# FiberLEDDouble.net
KiCad netlist of a schematic drawn in EAGLE
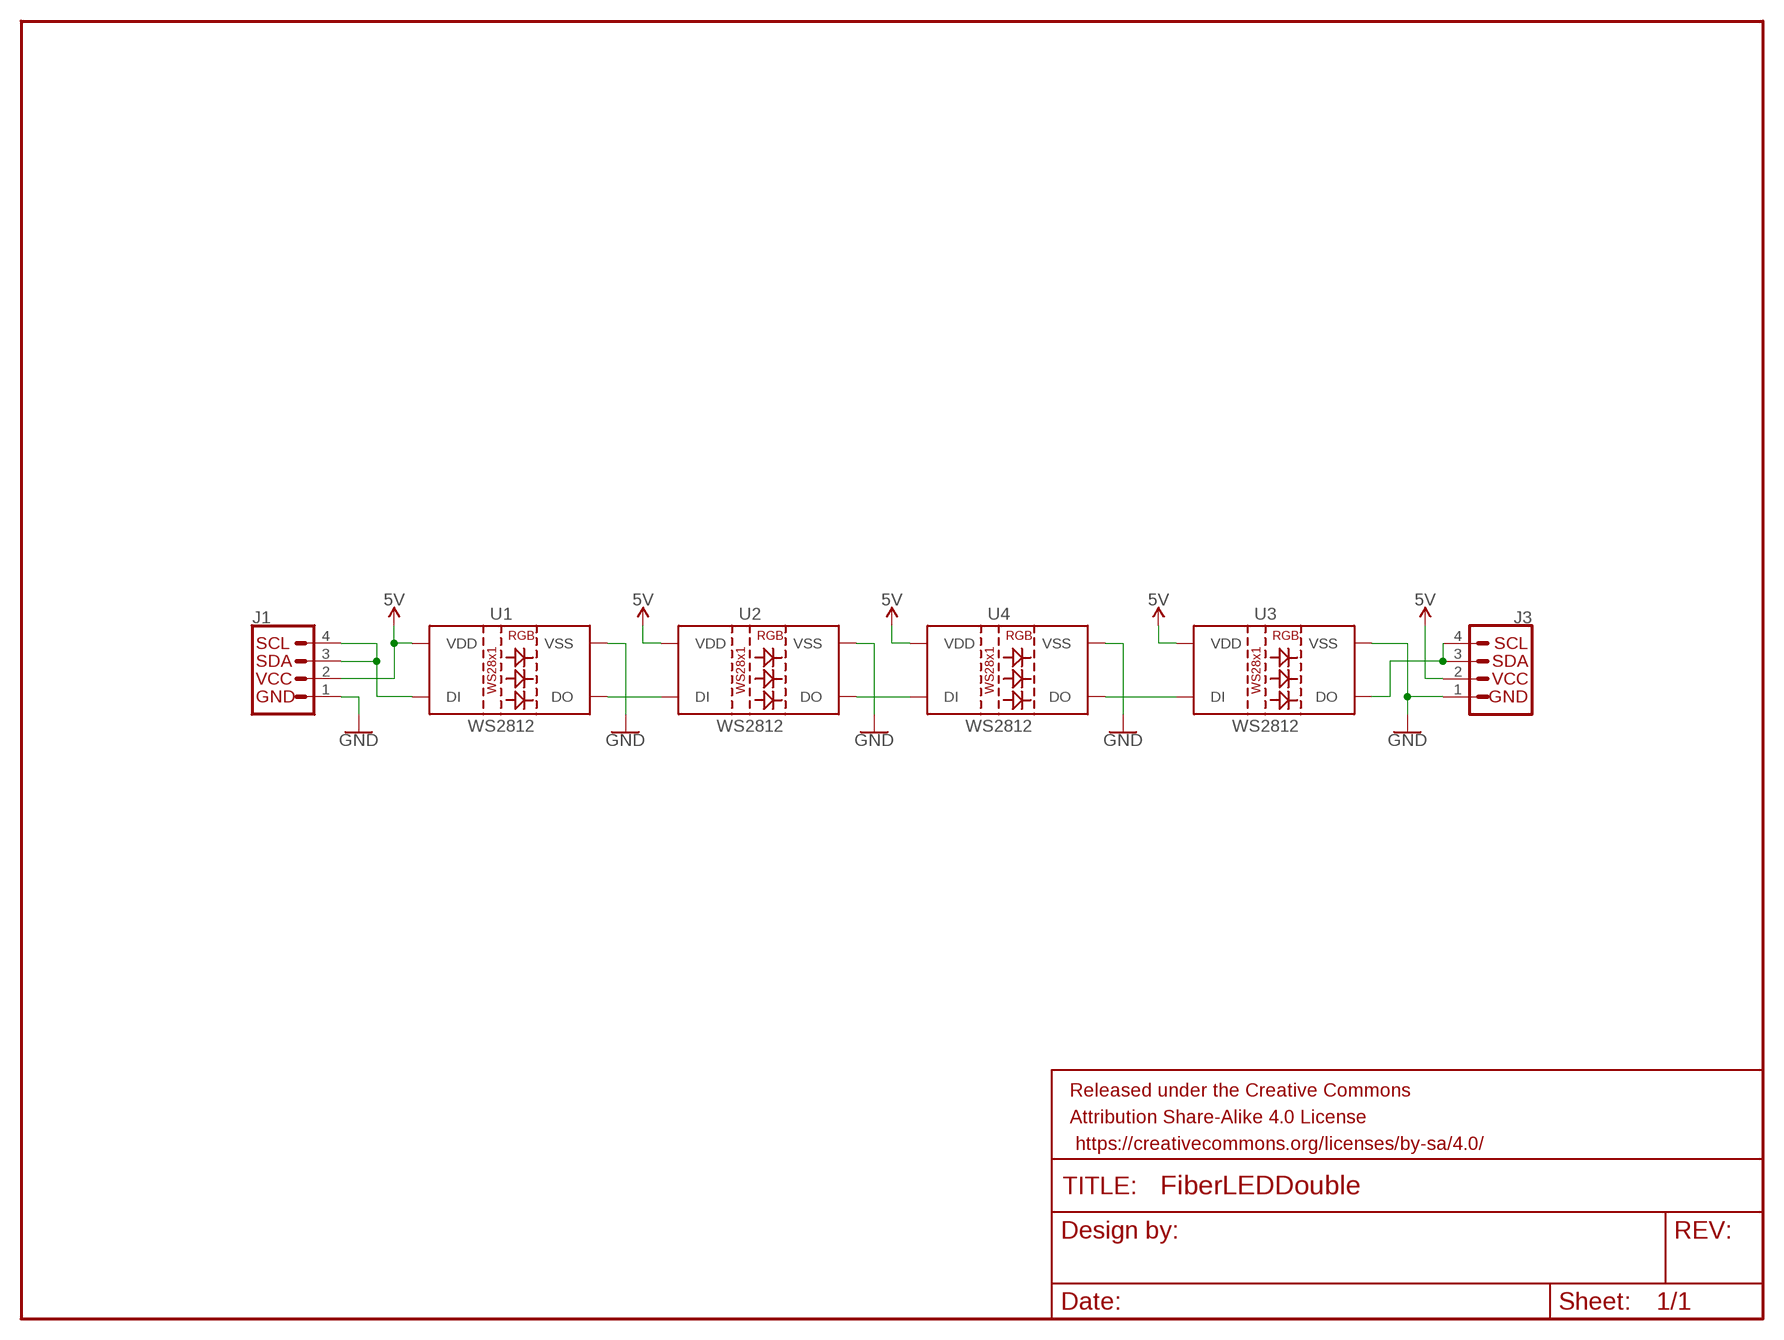
[diagram p0: schematic, sheet 1]

(export (version "E")
  (design (tool "Eeschema 10.0.6"))
  (components
    (comp (ref "FRAME1")
      (value "FRAME-LETTER")
      (footprint "eagle-import:CREATIVE_COMMONS")
      (libsource (lib "eagle-import") (part "FRAME-LETTER"))
    )
    (comp (ref "J1")
      (value "QWIIC_CONNECTORJS-1MM")
      (footprint "eagle-import:1X04_1MM_RA")
      (libsource (lib "eagle-import") (part "QWIIC_CONNECTORJS-1MM"))
    )
    (comp (ref "J3")
      (value "QWIIC_CONNECTORJS-1MM")
      (footprint "eagle-import:1X04_1MM_RA")
      (libsource (lib "eagle-import") (part "QWIIC_CONNECTORJS-1MM"))
    )
    (comp (ref "U1")
      (value "WS2812")
      (footprint "eagle-import:LED-TRICOLOR-5050-IC")
      (libsource (lib "eagle-import") (part "WS2812{dblquote}"))
    )
    (comp (ref "U2")
      (value "WS2812")
      (footprint "eagle-import:LED-TRICOLOR-5050-IC")
      (libsource (lib "eagle-import") (part "WS2812{dblquote}"))
    )
    (comp (ref "U3")
      (value "WS2812")
      (footprint "eagle-import:LED-TRICOLOR-5050-IC")
      (libsource (lib "eagle-import") (part "WS2812{dblquote}"))
    )
    (comp (ref "U4")
      (value "WS2812")
      (footprint "eagle-import:LED-TRICOLOR-5050-IC")
      (libsource (lib "eagle-import") (part "WS2812{dblquote}"))
    )
  )
  (nets
    (net (code "1") (name "5V") (class "Default")
      (node (ref "J1") (pin "2") (pinfunction "2_2") (pintype "power_in"))
      (node (ref "J3") (pin "2") (pinfunction "2_2") (pintype "power_in"))
      (node (ref "U1") (pin "3") (pinfunction "VDD_3") (pintype "bidirectional"))
      (node (ref "U1") (pin "5") (pinfunction "VDD_5") (pintype "bidirectional"))
      (node (ref "U2") (pin "3") (pinfunction "VDD_3") (pintype "bidirectional"))
      (node (ref "U2") (pin "5") (pinfunction "VDD_5") (pintype "bidirectional"))
      (node (ref "U3") (pin "3") (pinfunction "VDD_3") (pintype "bidirectional"))
      (node (ref "U3") (pin "5") (pinfunction "VDD_5") (pintype "bidirectional"))
      (node (ref "U4") (pin "3") (pinfunction "VDD_3") (pintype "bidirectional"))
      (node (ref "U4") (pin "5") (pinfunction "VDD_5") (pintype "bidirectional"))
    )
    (net (code "2") (name "GND") (class "Default")
      (node (ref "J1") (pin "1") (pinfunction "1_1") (pintype "power_in"))
      (node (ref "J3") (pin "1") (pinfunction "1_1") (pintype "power_in"))
      (node (ref "U1") (pin "6") (pinfunction "VSS_6") (pintype "bidirectional"))
      (node (ref "U2") (pin "6") (pinfunction "VSS_6") (pintype "bidirectional"))
      (node (ref "U3") (pin "6") (pinfunction "VSS_6") (pintype "bidirectional"))
      (node (ref "U4") (pin "6") (pinfunction "VSS_6") (pintype "bidirectional"))
    )
    (net (code "3") (name "Net-(U1-DI)") (class "Default")
      (node (ref "J1") (pin "3") (pinfunction "3_3") (pintype "passive"))
      (node (ref "J1") (pin "4") (pinfunction "4_4") (pintype "passive"))
      (node (ref "U1") (pin "2") (pinfunction "DI_2") (pintype "bidirectional"))
    )
    (net (code "4") (name "Net-(U1-DO)") (class "Default")
      (node (ref "U1") (pin "1") (pinfunction "DO_1") (pintype "bidirectional"))
      (node (ref "U2") (pin "2") (pinfunction "DI_2") (pintype "bidirectional"))
    )
    (net (code "5") (name "Net-(U2-DO)") (class "Default")
      (node (ref "U2") (pin "1") (pinfunction "DO_1") (pintype "bidirectional"))
      (node (ref "U4") (pin "2") (pinfunction "DI_2") (pintype "bidirectional"))
    )
    (net (code "6") (name "Net-(U3-DI)") (class "Default")
      (node (ref "U3") (pin "2") (pinfunction "DI_2") (pintype "bidirectional"))
      (node (ref "U4") (pin "1") (pinfunction "DO_1") (pintype "bidirectional"))
    )
    (net (code "7") (name "Net-(U3-DO)") (class "Default")
      (node (ref "J3") (pin "3") (pinfunction "3_3") (pintype "passive"))
      (node (ref "J3") (pin "4") (pinfunction "4_4") (pintype "passive"))
      (node (ref "U3") (pin "1") (pinfunction "DO_1") (pintype "bidirectional"))
    )
  )
)
